# RS232_NPN_PNP_Negative_2.net
KiCad netlist of a schematic drawn in EAGLE
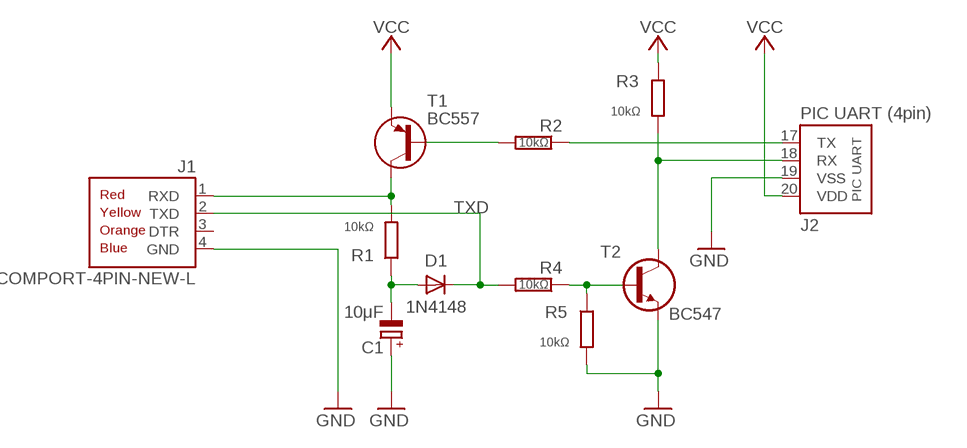
[diagram p0: schematic, sheet 1]

(export (version "E")
  (design (tool "Eeschema 10.0.6"))
  (components
    (comp (ref "C1")
      (value "10μF")
      (footprint "eagle-import:E2,5-3_V")
      (libsource (lib "eagle-import") (part "CPOLE2,5-3/V"))
    )
    (comp (ref "D1")
      (value "1N4148")
      (footprint "eagle-import:DO34-5")
      (libsource (lib "eagle-import") (part "1N414834-5"))
    )
    (comp (ref "J1")
      (value "COMPORT-4PIN-NEW-L")
      (footprint "eagle-import:RS232-4PIN-NEW-L")
      (libsource (lib "eagle-import") (part "COMPORT-4PIN-NEW-L"))
    )
    (comp (ref "J2")
      (value "PIC UART (4pin)")
      (footprint "eagle-import:PIC-UART")
      (libsource (lib "eagle-import") (part "PIC-UART"))
    )
    (comp (ref "R1")
      (value "10kΩ")
      (footprint "eagle-import:0202_7")
      (libsource (lib "eagle-import") (part "R0202/7"))
    )
    (comp (ref "R2")
      (value "10kΩ")
      (footprint "eagle-import:0202_10-V")
      (libsource (lib "eagle-import") (part "R0202/10-V"))
    )
    (comp (ref "R3")
      (value "10kΩ")
      (footprint "eagle-import:0202_7-V")
      (libsource (lib "eagle-import") (part "R0202/7-V"))
    )
    (comp (ref "R4")
      (value "10kΩ")
      (footprint "eagle-import:0202_7")
      (libsource (lib "eagle-import") (part "R0202/7"))
    )
    (comp (ref "R5")
      (value "10kΩ")
      (footprint "eagle-import:0202_7")
      (libsource (lib "eagle-import") (part "R0202/7"))
    )
    (comp (ref "T1")
      (value "BC557")
      (footprint "eagle-import:TO92-CBE")
      (libsource (lib "eagle-import") (part "BC557CBE"))
    )
    (comp (ref "T2")
      (value "BC547")
      (footprint "eagle-import:TO92-CBE")
      (libsource (lib "eagle-import") (part "BC547CBE"))
    )
  )
  (nets
    (net (code "1") (name "/TXD") (class "Default")
      (node (ref "D1") (pin "C") (pinfunction "C_C") (pintype "passive"))
      (node (ref "J1") (pin "2") (pinfunction "TXD_2") (pintype "passive"))
      (node (ref "R4") (pin "2") (pinfunction "2_2") (pintype "passive"))
    )
    (net (code "2") (name "GND") (class "Default")
      (node (ref "C1") (pin "+") (pinfunction "+_+") (pintype "passive"))
      (node (ref "J1") (pin "4") (pinfunction "GND_4") (pintype "passive"))
      (node (ref "J2") (pin "19") (pinfunction "VSS_19") (pintype "passive"))
      (node (ref "R5") (pin "2") (pinfunction "2_2") (pintype "passive"))
      (node (ref "T2") (pin "E") (pinfunction "E_E") (pintype "passive"))
    )
    (net (code "3") (name "Net-(C1-Pad-)") (class "Default")
      (node (ref "C1") (pin "-") (pinfunction "-_-") (pintype "passive"))
      (node (ref "D1") (pin "A") (pinfunction "A_A") (pintype "passive"))
      (node (ref "R1") (pin "1") (pinfunction "1_1") (pintype "passive"))
    )
    (net (code "4") (name "Net-(J1-RXD)") (class "Default")
      (node (ref "J1") (pin "1") (pinfunction "RXD_1") (pintype "passive"))
      (node (ref "R1") (pin "2") (pinfunction "2_2") (pintype "passive"))
      (node (ref "T1") (pin "C") (pinfunction "C_C") (pintype "passive"))
    )
    (net (code "5") (name "Net-(J2-RX)") (class "Default")
      (node (ref "J2") (pin "18") (pinfunction "RX_18") (pintype "passive"))
      (node (ref "R3") (pin "1") (pinfunction "1_1") (pintype "passive"))
      (node (ref "T2") (pin "C") (pinfunction "C_C") (pintype "passive"))
    )
    (net (code "6") (name "Net-(J2-TX)") (class "Default")
      (node (ref "J2") (pin "17") (pinfunction "TX_17") (pintype "passive"))
      (node (ref "R2") (pin "1") (pinfunction "1_1") (pintype "passive"))
    )
    (net (code "7") (name "Net-(R2-Pad2)") (class "Default")
      (node (ref "R2") (pin "2") (pinfunction "2_2") (pintype "passive"))
      (node (ref "T1") (pin "B") (pinfunction "B_B") (pintype "passive"))
    )
    (net (code "8") (name "Net-(R4-Pad1)") (class "Default")
      (node (ref "R4") (pin "1") (pinfunction "1_1") (pintype "passive"))
      (node (ref "R5") (pin "1") (pinfunction "1_1") (pintype "passive"))
      (node (ref "T2") (pin "B") (pinfunction "B_B") (pintype "passive"))
    )
    (net (code "9") (name "VCC") (class "Default")
      (node (ref "J2") (pin "20") (pinfunction "VDD_20") (pintype "passive"))
      (node (ref "R3") (pin "2") (pinfunction "2_2") (pintype "passive"))
      (node (ref "T1") (pin "E") (pinfunction "E_E") (pintype "passive"))
    )
    (net (code "10") (name "unconnected-(J1-DTR-Pad3)") (class "Default")
      (node (ref "J1") (pin "3") (pinfunction "DTR_3") (pintype "passive"))
    )
  )
)
